# Schematic.net
KiCad netlist of a schematic drawn in EasyEDA
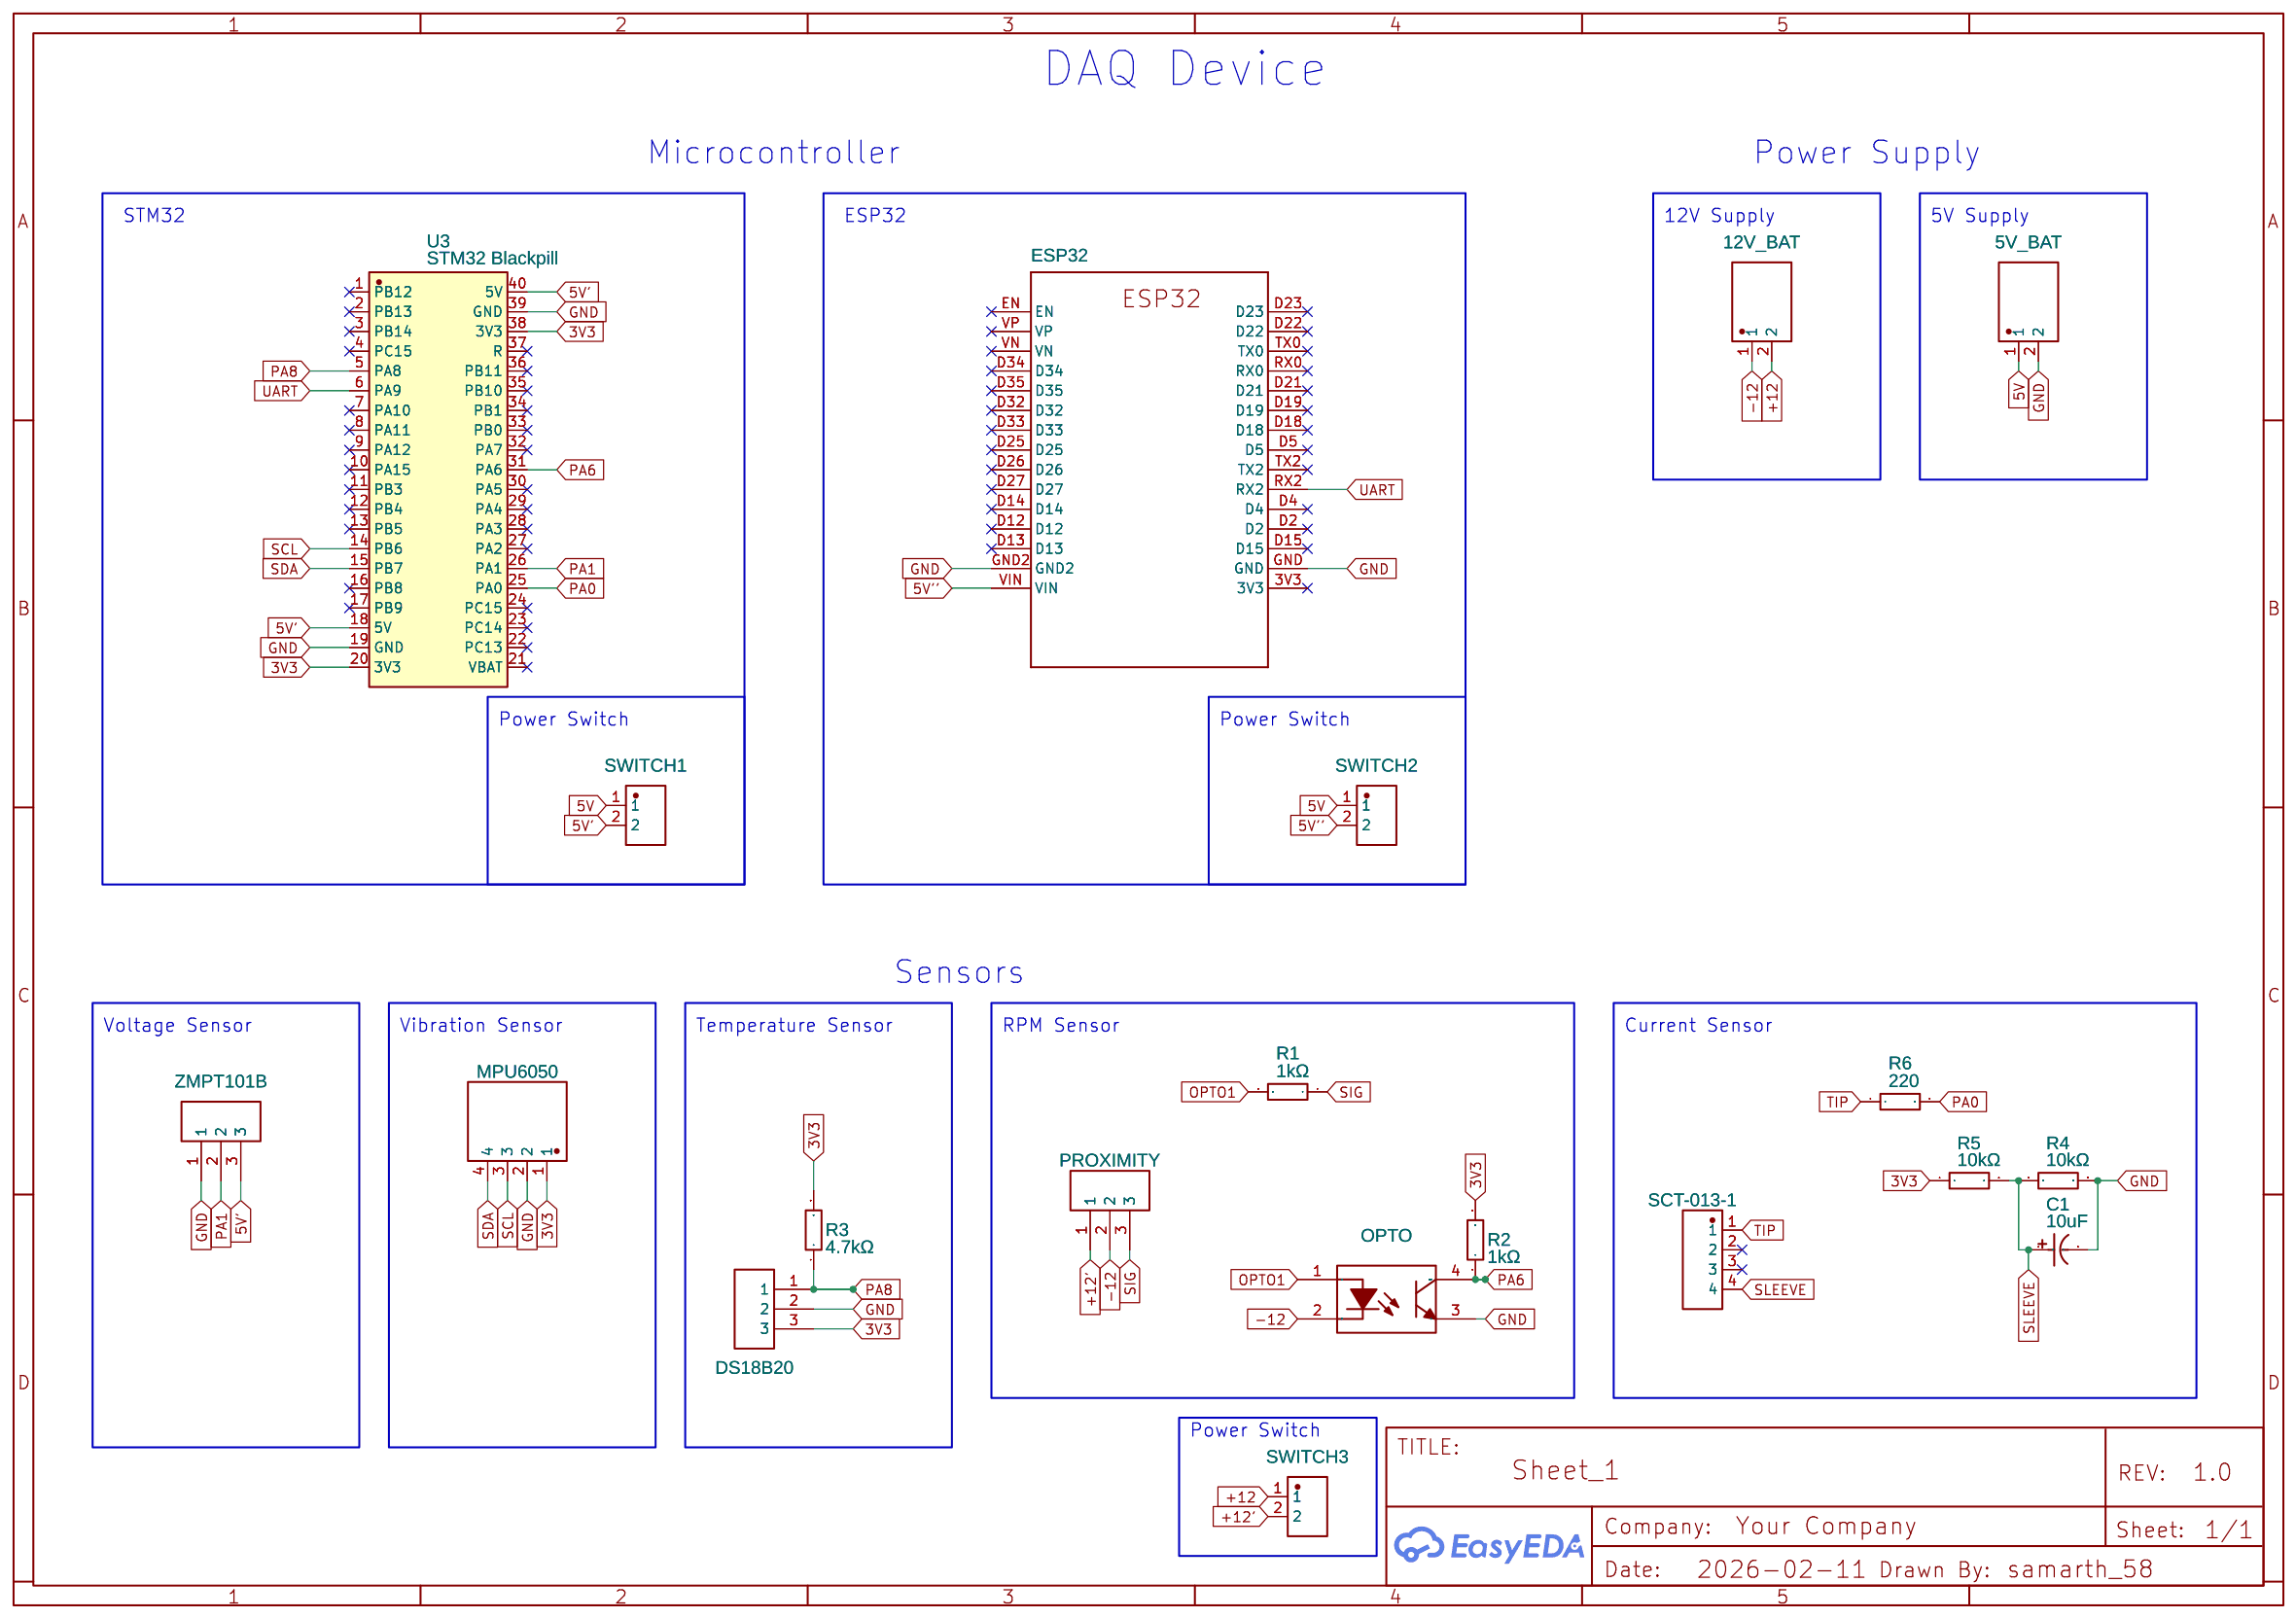
[diagram p0: schematic sheet]

(export (version "E")
  (design (tool "Eeschema 10.0.6"))
  (components
    (comp (ref "2") (value "ESP32") (libsource (lib "") (part "ESP32-DEVKIT-V1-30PIN")))
    (comp (ref "5V_BAT")
      (value "B2B-XH-A (LF)(SN)")
      (fields (field (name "Manufacturer Part") "B2B-XH-A(LF)(SN)") (field (name "Manufacturer") "JST"))
      (libsource (lib "") (part "B2B-XH-A (LF)(SN)"))
    )
    (comp (ref "12V_BAT")
      (value "B2B-XH-A (LF)(SN)")
      (fields (field (name "Manufacturer Part") "B2B-XH-A(LF)(SN)") (field (name "Manufacturer") "JST"))
      (libsource (lib "") (part "B2B-XH-A (LF)(SN)_1"))
    )
    (comp (ref "C1")
      (value "10uF")
      (fields
        (field (name "Manufacturer Part") "100YXF10MEFCT16.3X11")
        (field (name "Manufacturer") "Rubycon(红宝石)")
      )
      (libsource (lib "") (part "100YXF10MEFCT16.3X11"))
    )
    (comp (ref "DS18B20")
      (value "B3B-XH-A(LF)(SN)")
      (fields (field (name "Manufacturer") "JST"))
      (libsource (lib "") (part "B3B-XH-A(LF)(SN)_1"))
    )
    (comp (ref "MPU6050")
      (value "B4B-XH-A(LF)(SN)")
      (fields (field (name "Manufacturer") "JST"))
      (libsource (lib "") (part "B4B-XH-A(LF)(SN)"))
    )
    (comp (ref "OPTO")
      (value "PC817C_C20612594")
      (fields (field (name "Manufacturer Part") "PC817C") (field (name "Manufacturer") "AOTE(奥特)"))
      (libsource (lib "") (part "PC817C_C20612594"))
    )
    (comp (ref "PROXIMITY")
      (value "B3B-XH-A(LF)(SN)")
      (fields (field (name "Manufacturer") "JST"))
      (libsource (lib "") (part "B3B-XH-A(LF)(SN)_2"))
    )
    (comp (ref "R1")
      (value "1kΩ")
      (fields
        (field (name "Manufacturer Part") "MBB02070C1001FCT00")
        (field (name "Manufacturer") "VISHAY(威世)")
      )
      (libsource (lib "") (part "MBB02070C1001FCT00"))
    )
    (comp (ref "R2")
      (value "1kΩ")
      (fields
        (field (name "Manufacturer Part") "MBB02070C1001FCT00")
        (field (name "Manufacturer") "VISHAY(威世)")
      )
      (libsource (lib "") (part "MBB02070C1001FCT00_1"))
    )
    (comp (ref "R3")
      (value "4.7kΩ")
      (fields
        (field (name "Manufacturer Part") "MF1/4W-4.7KΩ±1% T")
        (field (name "Manufacturer") "CCO(千志电子)")
      )
      (libsource (lib "") (part "MF1/4W-4.7KΩ±1% T52"))
    )
    (comp (ref "R4")
      (value "10kΩ")
      (fields
        (field (name "Manufacturer Part") "MBB02070C1001FCT00")
        (field (name "Manufacturer") "VISHAY(威世)")
      )
      (libsource (lib "") (part "MBB02070C1001FCT00_2"))
    )
    (comp (ref "R5")
      (value "10kΩ")
      (fields
        (field (name "Manufacturer Part") "MBB02070C1001FCT00")
        (field (name "Manufacturer") "VISHAY(威世)")
      )
      (libsource (lib "") (part "MBB02070C1001FCT00_2"))
    )
    (comp (ref "R6")
      (value "220")
      (fields (field (name "Manufacturer Part") "MF1/4W-220Ω±1% T") (field (name "Manufacturer") "CCO(千志电子)"))
      (libsource (lib "") (part "MF1/4W-220__1% T"))
    )
    (comp (ref "SCT-013-1")
      (value "PM2.54-1*4")
      (fields (field (name "Manufacturer") "ZHOURI(洲日)"))
      (libsource (lib "") (part "PM2.54-1*4"))
    )
    (comp (ref "SWITCH1")
      (value "HX PH254-01-02-Z-L11.5 MALE HEADER CONNECTOR")
      (fields
        (field (name "Manufacturer Part") "HX PH254-01-02-Z-L11.5 male header connector")
        (field (name "Manufacturer") "hanxia(韩下)")
      )
      (libsource (lib "") (part "HX PH254-01-02-Z-L11.5 MALE HEADER CONNECTOR"))
    )
    (comp (ref "SWITCH2")
      (value "HX PH254-01-02-Z-L11.5 MALE HEADER CONNECTOR")
      (fields
        (field (name "Manufacturer Part") "HX PH254-01-02-Z-L11.5 male header connector")
        (field (name "Manufacturer") "hanxia(韩下)")
      )
      (libsource (lib "") (part "HX PH254-01-02-Z-L11.5 MALE HEADER CONNECTOR"))
    )
    (comp (ref "SWITCH3")
      (value "HX PH254-01-02-Z-L11.5 MALE HEADER CONNECTOR")
      (fields
        (field (name "Manufacturer Part") "HX PH254-01-02-Z-L11.5 male header connector")
        (field (name "Manufacturer") "hanxia(韩下)")
      )
      (libsource (lib "") (part "HX PH254-01-02-Z-L11.5 MALE HEADER CONNECTOR"))
    )
    (comp (ref "U3") (value "STM32 Blackpill") (libsource (lib "") (part "STM32 Blackpill")))
    (comp (ref "ZMPT101B")
      (value "B3B-XH-A(LF)(SN)")
      (fields (field (name "Manufacturer") "JST"))
      (libsource (lib "") (part "B3B-XH-A(LF)(SN)"))
    )
  )
  (nets
    (net (code "1") (name "+12") (class "Default")
      (node (ref "12V_BAT") (pin "2") (pinfunction "2_2") (pintype "unspecified"))
      (node (ref "SWITCH3") (pin "1") (pinfunction "1_1") (pintype "unspecified"))
    )
    (net (code "2") (name "+12'") (class "Default")
      (node (ref "PROXIMITY") (pin "1") (pinfunction "1_1") (pintype "unspecified"))
      (node (ref "SWITCH3") (pin "2") (pinfunction "2_2") (pintype "unspecified"))
    )
    (net (code "3") (name "-12") (class "Default")
      (node (ref "12V_BAT") (pin "1") (pinfunction "1_1") (pintype "unspecified"))
      (node (ref "OPTO") (pin "2") (pinfunction "C_2") (pintype "unspecified"))
      (node (ref "PROXIMITY") (pin "2") (pinfunction "2_2") (pintype "unspecified"))
    )
    (net (code "4") (name "3V3") (class "Default")
      (node (ref "DS18B20") (pin "3") (pinfunction "3_3") (pintype "unspecified"))
      (node (ref "MPU6050") (pin "1") (pinfunction "1_1") (pintype "unspecified"))
      (node (ref "R2") (pin "2") (pinfunction "2_2") (pintype "unspecified"))
      (node (ref "R3") (pin "2") (pinfunction "2_2") (pintype "unspecified"))
      (node (ref "R5") (pin "1") (pinfunction "1_1") (pintype "unspecified"))
      (node (ref "U3") (pin "20") (pinfunction "3V3_20") (pintype "unspecified"))
      (node (ref "U3") (pin "38") (pinfunction "3V3_38") (pintype "unspecified"))
    )
    (net (code "5") (name "5V") (class "Default")
      (node (ref "5V_BAT") (pin "1") (pinfunction "1_1") (pintype "unspecified"))
      (node (ref "SWITCH1") (pin "1") (pinfunction "1_1") (pintype "unspecified"))
      (node (ref "SWITCH2") (pin "1") (pinfunction "1_1") (pintype "unspecified"))
    )
    (net (code "6") (name "5V'") (class "Default")
      (node (ref "SWITCH1") (pin "2") (pinfunction "2_2") (pintype "unspecified"))
      (node (ref "U3") (pin "18") (pinfunction "5V_18") (pintype "unspecified"))
      (node (ref "U3") (pin "40") (pinfunction "5V_40") (pintype "unspecified"))
      (node (ref "ZMPT101B") (pin "3") (pinfunction "3_3") (pintype "unspecified"))
    )
    (net (code "7") (name "5V''") (class "Default")
      (node (ref "2") (pin "VIN") (pinfunction "VIN_VIN") (pintype "unspecified"))
      (node (ref "SWITCH2") (pin "2") (pinfunction "2_2") (pintype "unspecified"))
    )
    (net (code "8") (name "GND") (class "Default")
      (node (ref "2") (pin "GND") (pinfunction "GND_GND") (pintype "unspecified"))
      (node (ref "2") (pin "GND2") (pinfunction "GND2_GND2") (pintype "unspecified"))
      (node (ref "5V_BAT") (pin "2") (pinfunction "2_2") (pintype "unspecified"))
      (node (ref "C1") (pin "2") (pinfunction "2_2") (pintype "input"))
      (node (ref "DS18B20") (pin "2") (pinfunction "2_2") (pintype "unspecified"))
      (node (ref "MPU6050") (pin "2") (pinfunction "2_2") (pintype "unspecified"))
      (node (ref "OPTO") (pin "3") (pinfunction "E_3") (pintype "unspecified"))
      (node (ref "R4") (pin "2") (pinfunction "2_2") (pintype "unspecified"))
      (node (ref "U3") (pin "19") (pinfunction "GND_19") (pintype "unspecified"))
      (node (ref "U3") (pin "39") (pinfunction "GND_39") (pintype "unspecified"))
      (node (ref "ZMPT101B") (pin "1") (pinfunction "1_1") (pintype "unspecified"))
    )
    (net (code "9") (name "OPTO1") (class "Default")
      (node (ref "OPTO") (pin "1") (pinfunction "A_1") (pintype "unspecified"))
      (node (ref "R1") (pin "2") (pinfunction "2_2") (pintype "unspecified"))
    )
    (net (code "10") (name "PA0") (class "Default")
      (node (ref "R6") (pin "2") (pinfunction "2_2") (pintype "unspecified"))
      (node (ref "U3") (pin "25") (pinfunction "PA0_25") (pintype "unspecified"))
    )
    (net (code "11") (name "PA1") (class "Default")
      (node (ref "U3") (pin "26") (pinfunction "PA1_26") (pintype "unspecified"))
      (node (ref "ZMPT101B") (pin "2") (pinfunction "2_2") (pintype "unspecified"))
    )
    (net (code "12") (name "PA6") (class "Default")
      (node (ref "OPTO") (pin "4") (pinfunction "COLLECTOR_4") (pintype "unspecified"))
      (node (ref "R2") (pin "1") (pinfunction "1_1") (pintype "unspecified"))
      (node (ref "U3") (pin "31") (pinfunction "PA6_31") (pintype "unspecified"))
    )
    (net (code "13") (name "PA8") (class "Default")
      (node (ref "DS18B20") (pin "1") (pinfunction "1_1") (pintype "unspecified"))
      (node (ref "R3") (pin "1") (pinfunction "1_1") (pintype "unspecified"))
      (node (ref "U3") (pin "5") (pinfunction "PA8_5") (pintype "unspecified"))
    )
    (net (code "14") (name "SCL") (class "Default")
      (node (ref "MPU6050") (pin "3") (pinfunction "3_3") (pintype "unspecified"))
      (node (ref "U3") (pin "14") (pinfunction "PB6_14") (pintype "unspecified"))
    )
    (net (code "15") (name "SDA") (class "Default")
      (node (ref "MPU6050") (pin "4") (pinfunction "4_4") (pintype "unspecified"))
      (node (ref "U3") (pin "15") (pinfunction "PB7_15") (pintype "unspecified"))
    )
    (net (code "16") (name "SIG") (class "Default")
      (node (ref "PROXIMITY") (pin "3") (pinfunction "3_3") (pintype "unspecified"))
      (node (ref "R1") (pin "1") (pinfunction "1_1") (pintype "unspecified"))
    )
    (net (code "17") (name "SLEEVE") (class "Default")
      (node (ref "C1") (pin "1") (pinfunction "1_1") (pintype "input"))
      (node (ref "R4") (pin "1") (pinfunction "1_1") (pintype "unspecified"))
      (node (ref "R5") (pin "2") (pinfunction "2_2") (pintype "unspecified"))
      (node (ref "SCT-013-1") (pin "4") (pinfunction "4_4") (pintype "unspecified"))
    )
    (net (code "18") (name "TIP") (class "Default")
      (node (ref "R6") (pin "1") (pinfunction "1_1") (pintype "unspecified"))
      (node (ref "SCT-013-1") (pin "1") (pinfunction "1_1") (pintype "unspecified"))
    )
    (net (code "19") (name "UART") (class "Default")
      (node (ref "2") (pin "RX2") (pinfunction "RX2_RX2") (pintype "unspecified"))
      (node (ref "U3") (pin "6") (pinfunction "PA9_6") (pintype "unspecified"))
    )
    (net (code "20") (name "unconnected-(2-Pad3V3)") (class "Default")
      (node (ref "2") (pin "3V3") (pinfunction "3V3_3V3") (pintype "unspecified+no_connect"))
    )
    (net (code "21") (name "unconnected-(2-PadD2)") (class "Default")
      (node (ref "2") (pin "D2") (pinfunction "D2_D2") (pintype "unspecified+no_connect"))
    )
    (net (code "22") (name "unconnected-(2-PadD4)") (class "Default")
      (node (ref "2") (pin "D4") (pinfunction "D4_D4") (pintype "unspecified+no_connect"))
    )
    (net (code "23") (name "unconnected-(2-PadD5)") (class "Default")
      (node (ref "2") (pin "D5") (pinfunction "D5_D5") (pintype "unspecified+no_connect"))
    )
    (net (code "24") (name "unconnected-(2-PadD12)") (class "Default")
      (node (ref "2") (pin "D12") (pinfunction "D12_D12") (pintype "unspecified+no_connect"))
    )
    (net (code "25") (name "unconnected-(2-PadD13)") (class "Default")
      (node (ref "2") (pin "D13") (pinfunction "D13_D13") (pintype "unspecified+no_connect"))
    )
    (net (code "26") (name "unconnected-(2-PadD14)") (class "Default")
      (node (ref "2") (pin "D14") (pinfunction "D14_D14") (pintype "unspecified+no_connect"))
    )
    (net (code "27") (name "unconnected-(2-PadD15)") (class "Default")
      (node (ref "2") (pin "D15") (pinfunction "D15_D15") (pintype "unspecified+no_connect"))
    )
    (net (code "28") (name "unconnected-(2-PadD18)") (class "Default")
      (node (ref "2") (pin "D18") (pinfunction "D18_D18") (pintype "unspecified+no_connect"))
    )
    (net (code "29") (name "unconnected-(2-PadD19)") (class "Default")
      (node (ref "2") (pin "D19") (pinfunction "D19_D19") (pintype "unspecified+no_connect"))
    )
    (net (code "30") (name "unconnected-(2-PadD21)") (class "Default")
      (node (ref "2") (pin "D21") (pinfunction "D21_D21") (pintype "unspecified+no_connect"))
    )
    (net (code "31") (name "unconnected-(2-PadD22)") (class "Default")
      (node (ref "2") (pin "D22") (pinfunction "D22_D22") (pintype "unspecified+no_connect"))
    )
    (net (code "32") (name "unconnected-(2-PadD23)") (class "Default")
      (node (ref "2") (pin "D23") (pinfunction "D23_D23") (pintype "unspecified+no_connect"))
    )
    (net (code "33") (name "unconnected-(2-PadD25)") (class "Default")
      (node (ref "2") (pin "D25") (pinfunction "D25_D25") (pintype "unspecified+no_connect"))
    )
    (net (code "34") (name "unconnected-(2-PadD26)") (class "Default")
      (node (ref "2") (pin "D26") (pinfunction "D26_D26") (pintype "unspecified+no_connect"))
    )
    (net (code "35") (name "unconnected-(2-PadD27)") (class "Default")
      (node (ref "2") (pin "D27") (pinfunction "D27_D27") (pintype "unspecified+no_connect"))
    )
    (net (code "36") (name "unconnected-(2-PadD32)") (class "Default")
      (node (ref "2") (pin "D32") (pinfunction "D32_D32") (pintype "unspecified+no_connect"))
    )
    (net (code "37") (name "unconnected-(2-PadD33)") (class "Default")
      (node (ref "2") (pin "D33") (pinfunction "D33_D33") (pintype "unspecified+no_connect"))
    )
    (net (code "38") (name "unconnected-(2-PadD34)") (class "Default")
      (node (ref "2") (pin "D34") (pinfunction "D34_D34") (pintype "unspecified+no_connect"))
    )
    (net (code "39") (name "unconnected-(2-PadD35)") (class "Default")
      (node (ref "2") (pin "D35") (pinfunction "D35_D35") (pintype "unspecified+no_connect"))
    )
    (net (code "40") (name "unconnected-(2-PadEN)") (class "Default")
      (node (ref "2") (pin "EN") (pinfunction "EN_EN") (pintype "unspecified+no_connect"))
    )
    (net (code "41") (name "unconnected-(2-PadRX0)") (class "Default")
      (node (ref "2") (pin "RX0") (pinfunction "RX0_RX0") (pintype "unspecified+no_connect"))
    )
    (net (code "42") (name "unconnected-(2-PadTX0)") (class "Default")
      (node (ref "2") (pin "TX0") (pinfunction "TX0_TX0") (pintype "unspecified+no_connect"))
    )
    (net (code "43") (name "unconnected-(2-PadTX2)") (class "Default")
      (node (ref "2") (pin "TX2") (pinfunction "TX2_TX2") (pintype "unspecified+no_connect"))
    )
    (net (code "44") (name "unconnected-(2-PadVN)") (class "Default")
      (node (ref "2") (pin "VN") (pinfunction "VN_VN") (pintype "unspecified+no_connect"))
    )
    (net (code "45") (name "unconnected-(2-PadVP)") (class "Default")
      (node (ref "2") (pin "VP") (pinfunction "VP_VP") (pintype "unspecified+no_connect"))
    )
    (net (code "46") (name "unconnected-(SCT-013-1-Pad2)") (class "Default")
      (node (ref "SCT-013-1") (pin "2") (pinfunction "2_2") (pintype "unspecified+no_connect"))
    )
    (net (code "47") (name "unconnected-(SCT-013-1-Pad3)") (class "Default")
      (node (ref "SCT-013-1") (pin "3") (pinfunction "3_3") (pintype "unspecified+no_connect"))
    )
    (net (code "48") (name "unconnected-(U3-PA2-Pad27)") (class "Default")
      (node (ref "U3") (pin "27") (pinfunction "PA2_27") (pintype "unspecified+no_connect"))
    )
    (net (code "49") (name "unconnected-(U3-PA3-Pad28)") (class "Default")
      (node (ref "U3") (pin "28") (pinfunction "PA3_28") (pintype "unspecified+no_connect"))
    )
    (net (code "50") (name "unconnected-(U3-PA4-Pad29)") (class "Default")
      (node (ref "U3") (pin "29") (pinfunction "PA4_29") (pintype "unspecified+no_connect"))
    )
    (net (code "51") (name "unconnected-(U3-PA5-Pad30)") (class "Default")
      (node (ref "U3") (pin "30") (pinfunction "PA5_30") (pintype "unspecified+no_connect"))
    )
    (net (code "52") (name "unconnected-(U3-PA7-Pad32)") (class "Default")
      (node (ref "U3") (pin "32") (pinfunction "PA7_32") (pintype "unspecified+no_connect"))
    )
    (net (code "53") (name "unconnected-(U3-PA10-Pad7)") (class "Default")
      (node (ref "U3") (pin "7") (pinfunction "PA10_7") (pintype "unspecified+no_connect"))
    )
    (net (code "54") (name "unconnected-(U3-PA11-Pad8)") (class "Default")
      (node (ref "U3") (pin "8") (pinfunction "PA11_8") (pintype "unspecified+no_connect"))
    )
    (net (code "55") (name "unconnected-(U3-PA12-Pad9)") (class "Default")
      (node (ref "U3") (pin "9") (pinfunction "PA12_9") (pintype "unspecified+no_connect"))
    )
    (net (code "56") (name "unconnected-(U3-PA15-Pad10)") (class "Default")
      (node (ref "U3") (pin "10") (pinfunction "PA15_10") (pintype "unspecified+no_connect"))
    )
    (net (code "57") (name "unconnected-(U3-PB0-Pad33)") (class "Default")
      (node (ref "U3") (pin "33") (pinfunction "PB0_33") (pintype "unspecified+no_connect"))
    )
    (net (code "58") (name "unconnected-(U3-PB1-Pad34)") (class "Default")
      (node (ref "U3") (pin "34") (pinfunction "PB1_34") (pintype "unspecified+no_connect"))
    )
    (net (code "59") (name "unconnected-(U3-PB3-Pad11)") (class "Default")
      (node (ref "U3") (pin "11") (pinfunction "PB3_11") (pintype "unspecified+no_connect"))
    )
    (net (code "60") (name "unconnected-(U3-PB4-Pad12)") (class "Default")
      (node (ref "U3") (pin "12") (pinfunction "PB4_12") (pintype "unspecified+no_connect"))
    )
    (net (code "61") (name "unconnected-(U3-PB5-Pad13)") (class "Default")
      (node (ref "U3") (pin "13") (pinfunction "PB5_13") (pintype "unspecified+no_connect"))
    )
    (net (code "62") (name "unconnected-(U3-PB8-Pad16)") (class "Default")
      (node (ref "U3") (pin "16") (pinfunction "PB8_16") (pintype "unspecified+no_connect"))
    )
    (net (code "63") (name "unconnected-(U3-PB9-Pad17)") (class "Default")
      (node (ref "U3") (pin "17") (pinfunction "PB9_17") (pintype "unspecified+no_connect"))
    )
    (net (code "64") (name "unconnected-(U3-PB10-Pad35)") (class "Default")
      (node (ref "U3") (pin "35") (pinfunction "PB10_35") (pintype "unspecified+no_connect"))
    )
    (net (code "65") (name "unconnected-(U3-PB11-Pad36)") (class "Default")
      (node (ref "U3") (pin "36") (pinfunction "PB11_36") (pintype "unspecified+no_connect"))
    )
    (net (code "66") (name "unconnected-(U3-PB12-Pad1)") (class "Default")
      (node (ref "U3") (pin "1") (pinfunction "PB12_1") (pintype "unspecified+no_connect"))
    )
    (net (code "67") (name "unconnected-(U3-PB13-Pad2)") (class "Default")
      (node (ref "U3") (pin "2") (pinfunction "PB13_2") (pintype "unspecified+no_connect"))
    )
    (net (code "68") (name "unconnected-(U3-PB14-Pad3)") (class "Default")
      (node (ref "U3") (pin "3") (pinfunction "PB14_3") (pintype "unspecified+no_connect"))
    )
    (net (code "69") (name "unconnected-(U3-PC13-Pad22)") (class "Default")
      (node (ref "U3") (pin "22") (pinfunction "PC13_22") (pintype "unspecified+no_connect"))
    )
    (net (code "70") (name "unconnected-(U3-PC14-Pad23)") (class "Default")
      (node (ref "U3") (pin "23") (pinfunction "PC14_23") (pintype "unspecified+no_connect"))
    )
    (net (code "71") (name "unconnected-(U3-PC15-Pad4)") (class "Default")
      (node (ref "U3") (pin "4") (pinfunction "PC15_4") (pintype "unspecified+no_connect"))
    )
    (net (code "72") (name "unconnected-(U3-PC15-Pad24)") (class "Default")
      (node (ref "U3") (pin "24") (pinfunction "PC15_24") (pintype "unspecified+no_connect"))
    )
    (net (code "73") (name "unconnected-(U3-R-Pad37)") (class "Default")
      (node (ref "U3") (pin "37") (pinfunction "R_37") (pintype "unspecified+no_connect"))
    )
    (net (code "74") (name "unconnected-(U3-VBAT-Pad21)") (class "Default")
      (node (ref "U3") (pin "21") (pinfunction "VBAT_21") (pintype "unspecified+no_connect"))
    )
  )
)
